# dhunter_bike.net
KiCad netlist of a schematic drawn in EAGLE
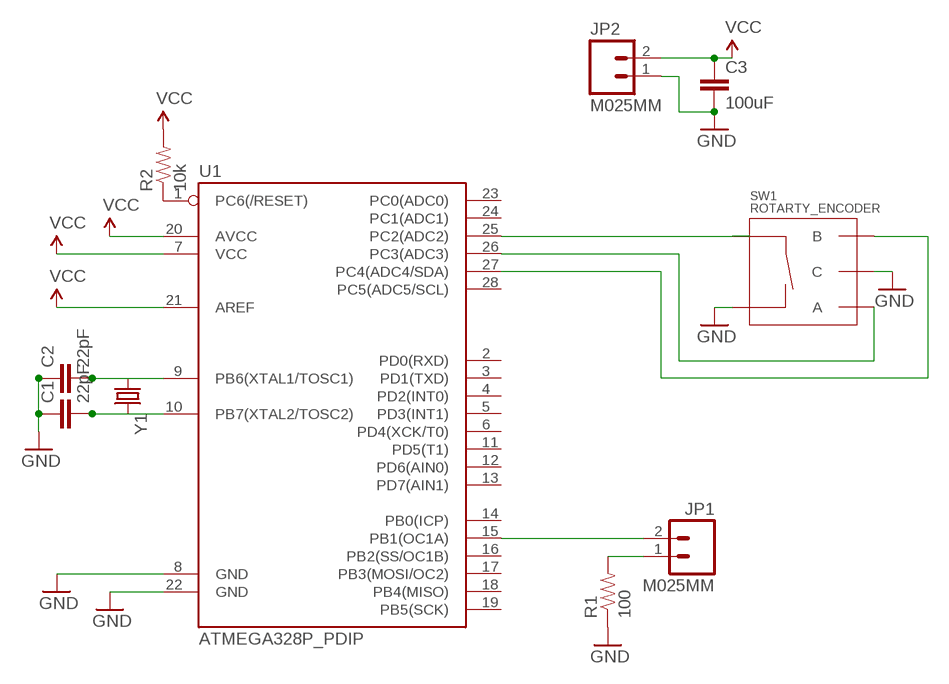
[diagram p0: schematic, sheet 1]

(export (version "E")
  (design (tool "Eeschema 10.0.6"))
  (components
    (comp (ref "C1")
      (value "22pF")
      (footprint "eagle-import:CAP-PTH-SMALLEZ")
      (libsource (lib "eagle-import") (part "CAPEZ"))
    )
    (comp (ref "C2")
      (value "22pF")
      (footprint "eagle-import:CAP-PTH-SMALLEZ")
      (libsource (lib "eagle-import") (part "CAPEZ"))
    )
    (comp (ref "C3")
      (value "100uF")
      (footprint "eagle-import:CAP-PTH-SMALLEZ")
      (libsource (lib "eagle-import") (part "CAPEZ"))
    )
    (comp (ref "JP1")
      (value "M025MM")
      (footprint "eagle-import:SCREWTERMINAL-5MM-2")
      (libsource (lib "eagle-import") (part "M025MM"))
    )
    (comp (ref "JP2")
      (value "M025MM")
      (footprint "eagle-import:SCREWTERMINAL-5MM-2")
      (libsource (lib "eagle-import") (part "M025MM"))
    )
    (comp (ref "R1")
      (value "100")
      (footprint "eagle-import:AXIAL-0.3EZ")
      (libsource (lib "eagle-import") (part "RESISTOREZ"))
    )
    (comp (ref "R2")
      (value "10k")
      (footprint "eagle-import:AXIAL-0.3EZ")
      (libsource (lib "eagle-import") (part "RESISTOREZ"))
    )
    (comp (ref "SW1")
      (value "ROTARTY_ENCODER")
      (footprint "eagle-import:ROTARY_ENC_PLAIN")
      (libsource (lib "eagle-import") (part "ROTARTY_ENCODER"))
    )
    (comp (ref "U1")
      (value "ATMEGA328P_PDIP")
      (footprint "eagle-import:DIL28-3")
      (libsource (lib "eagle-import") (part "ATMEGA328P_PDIP"))
    )
    (comp (ref "Y1")
      (value "CRYSTALHC49US")
      (footprint "eagle-import:HC49US")
      (libsource (lib "eagle-import") (part "CRYSTALHC49US"))
    )
  )
  (nets
    (net (code "1") (name "GND") (class "Default")
      (node (ref "C1") (pin "1") (pinfunction "1_1") (pintype "passive"))
      (node (ref "C2") (pin "1") (pinfunction "1_1") (pintype "passive"))
      (node (ref "C3") (pin "2") (pinfunction "2_2") (pintype "passive"))
      (node (ref "JP2") (pin "1") (pinfunction "1_1") (pintype "passive"))
      (node (ref "R1") (pin "P$1") (pinfunction "1_P$1") (pintype "passive"))
      (node (ref "SW1") (pin "C") (pinfunction "C_C") (pintype "bidirectional"))
      (node (ref "SW1") (pin "SW-") (pinfunction "SW-_SW-") (pintype "bidirectional"))
      (node (ref "U1") (pin "22") (pinfunction "GND_22") (pintype "bidirectional"))
      (node (ref "U1") (pin "8") (pinfunction "GND_8") (pintype "bidirectional"))
    )
    (net (code "2") (name "Net-(R1-2)") (class "Default")
      (node (ref "JP1") (pin "1") (pinfunction "1_1") (pintype "passive"))
      (node (ref "R1") (pin "P$2") (pinfunction "2_P$2") (pintype "passive"))
    )
    (net (code "3") (name "Net-(R2-1)") (class "Default")
      (node (ref "R2") (pin "P$1") (pinfunction "1_P$1") (pintype "passive"))
      (node (ref "U1") (pin "1") (pinfunction "PC6(/RESET)_1") (pintype "bidirectional"))
    )
    (net (code "4") (name "Net-(U1-PB1(OC1A))") (class "Default")
      (node (ref "JP1") (pin "2") (pinfunction "2_2") (pintype "passive"))
      (node (ref "U1") (pin "15") (pinfunction "PB1(OC1A)_15") (pintype "bidirectional"))
    )
    (net (code "5") (name "Net-(U1-PB6(XTAL1{slash}TOSC1))") (class "Default")
      (node (ref "C2") (pin "2") (pinfunction "2_2") (pintype "passive"))
      (node (ref "U1") (pin "9") (pinfunction "PB6(XTAL1/TOSC1)_9") (pintype "bidirectional"))
      (node (ref "Y1") (pin "1") (pinfunction "1_1") (pintype "passive"))
    )
    (net (code "6") (name "Net-(U1-PB7(XTAL2{slash}TOSC2))") (class "Default")
      (node (ref "C1") (pin "2") (pinfunction "2_2") (pintype "passive"))
      (node (ref "U1") (pin "10") (pinfunction "PB7(XTAL2/TOSC2)_10") (pintype "bidirectional"))
      (node (ref "Y1") (pin "2") (pinfunction "2_2") (pintype "passive"))
    )
    (net (code "7") (name "Net-(U1-PC2(ADC2))") (class "Default")
      (node (ref "SW1") (pin "SW+") (pinfunction "SW+_SW+") (pintype "bidirectional"))
      (node (ref "U1") (pin "25") (pinfunction "PC2(ADC2)_25") (pintype "bidirectional"))
    )
    (net (code "8") (name "Net-(U1-PC3(ADC3))") (class "Default")
      (node (ref "SW1") (pin "A") (pinfunction "A_A") (pintype "bidirectional"))
      (node (ref "U1") (pin "26") (pinfunction "PC3(ADC3)_26") (pintype "bidirectional"))
    )
    (net (code "9") (name "Net-(U1-PC4(ADC4{slash}SDA))") (class "Default")
      (node (ref "SW1") (pin "B") (pinfunction "B_B") (pintype "bidirectional"))
      (node (ref "U1") (pin "27") (pinfunction "PC4(ADC4/SDA)_27") (pintype "bidirectional"))
    )
    (net (code "10") (name "VCC") (class "Default")
      (node (ref "C3") (pin "1") (pinfunction "1_1") (pintype "passive"))
      (node (ref "JP2") (pin "2") (pinfunction "2_2") (pintype "passive"))
      (node (ref "R2") (pin "P$2") (pinfunction "2_P$2") (pintype "passive"))
      (node (ref "U1") (pin "20") (pinfunction "AVCC_20") (pintype "bidirectional"))
      (node (ref "U1") (pin "21") (pinfunction "AREF_21") (pintype "bidirectional"))
      (node (ref "U1") (pin "7") (pinfunction "VCC_7") (pintype "bidirectional"))
    )
    (net (code "11") (name "unconnected-(U1-PB0(ICP)-Pad14)") (class "Default")
      (node (ref "U1") (pin "14") (pinfunction "PB0(ICP)_14") (pintype "bidirectional"))
    )
    (net (code "12") (name "unconnected-(U1-PB2(SS{slash}OC1B)-Pad16)") (class "Default")
      (node (ref "U1") (pin "16") (pinfunction "PB2(SS/OC1B)_16") (pintype "bidirectional"))
    )
    (net (code "13") (name "unconnected-(U1-PB3(MOSI{slash}OC2)-Pad17)") (class "Default")
      (node (ref "U1") (pin "17") (pinfunction "PB3(MOSI/OC2)_17") (pintype "bidirectional"))
    )
    (net (code "14") (name "unconnected-(U1-PB4(MISO)-Pad18)") (class "Default")
      (node (ref "U1") (pin "18") (pinfunction "PB4(MISO)_18") (pintype "bidirectional"))
    )
    (net (code "15") (name "unconnected-(U1-PB5(SCK)-Pad19)") (class "Default")
      (node (ref "U1") (pin "19") (pinfunction "PB5(SCK)_19") (pintype "bidirectional"))
    )
    (net (code "16") (name "unconnected-(U1-PC0(ADC0)-Pad23)") (class "Default")
      (node (ref "U1") (pin "23") (pinfunction "PC0(ADC0)_23") (pintype "bidirectional"))
    )
    (net (code "17") (name "unconnected-(U1-PC1(ADC1)-Pad24)") (class "Default")
      (node (ref "U1") (pin "24") (pinfunction "PC1(ADC1)_24") (pintype "bidirectional"))
    )
    (net (code "18") (name "unconnected-(U1-PC5(ADC5{slash}SCL)-Pad28)") (class "Default")
      (node (ref "U1") (pin "28") (pinfunction "PC5(ADC5/SCL)_28") (pintype "bidirectional"))
    )
    (net (code "19") (name "unconnected-(U1-PD0(RXD)-Pad2)") (class "Default")
      (node (ref "U1") (pin "2") (pinfunction "PD0(RXD)_2") (pintype "bidirectional"))
    )
    (net (code "20") (name "unconnected-(U1-PD1(TXD)-Pad3)") (class "Default")
      (node (ref "U1") (pin "3") (pinfunction "PD1(TXD)_3") (pintype "bidirectional"))
    )
    (net (code "21") (name "unconnected-(U1-PD2(INT0)-Pad4)") (class "Default")
      (node (ref "U1") (pin "4") (pinfunction "PD2(INT0)_4") (pintype "bidirectional"))
    )
    (net (code "22") (name "unconnected-(U1-PD3(INT1)-Pad5)") (class "Default")
      (node (ref "U1") (pin "5") (pinfunction "PD3(INT1)_5") (pintype "bidirectional"))
    )
    (net (code "23") (name "unconnected-(U1-PD4(XCK{slash}T0)-Pad6)") (class "Default")
      (node (ref "U1") (pin "6") (pinfunction "PD4(XCK/T0)_6") (pintype "bidirectional"))
    )
    (net (code "24") (name "unconnected-(U1-PD5(T1)-Pad11)") (class "Default")
      (node (ref "U1") (pin "11") (pinfunction "PD5(T1)_11") (pintype "bidirectional"))
    )
    (net (code "25") (name "unconnected-(U1-PD6(AIN0)-Pad12)") (class "Default")
      (node (ref "U1") (pin "12") (pinfunction "PD6(AIN0)_12") (pintype "bidirectional"))
    )
    (net (code "26") (name "unconnected-(U1-PD7(AIN1)-Pad13)") (class "Default")
      (node (ref "U1") (pin "13") (pinfunction "PD7(AIN1)_13") (pintype "bidirectional"))
    )
  )
)
